# ESP32_Breakout.net
KiCad netlist of a schematic drawn in EAGLE
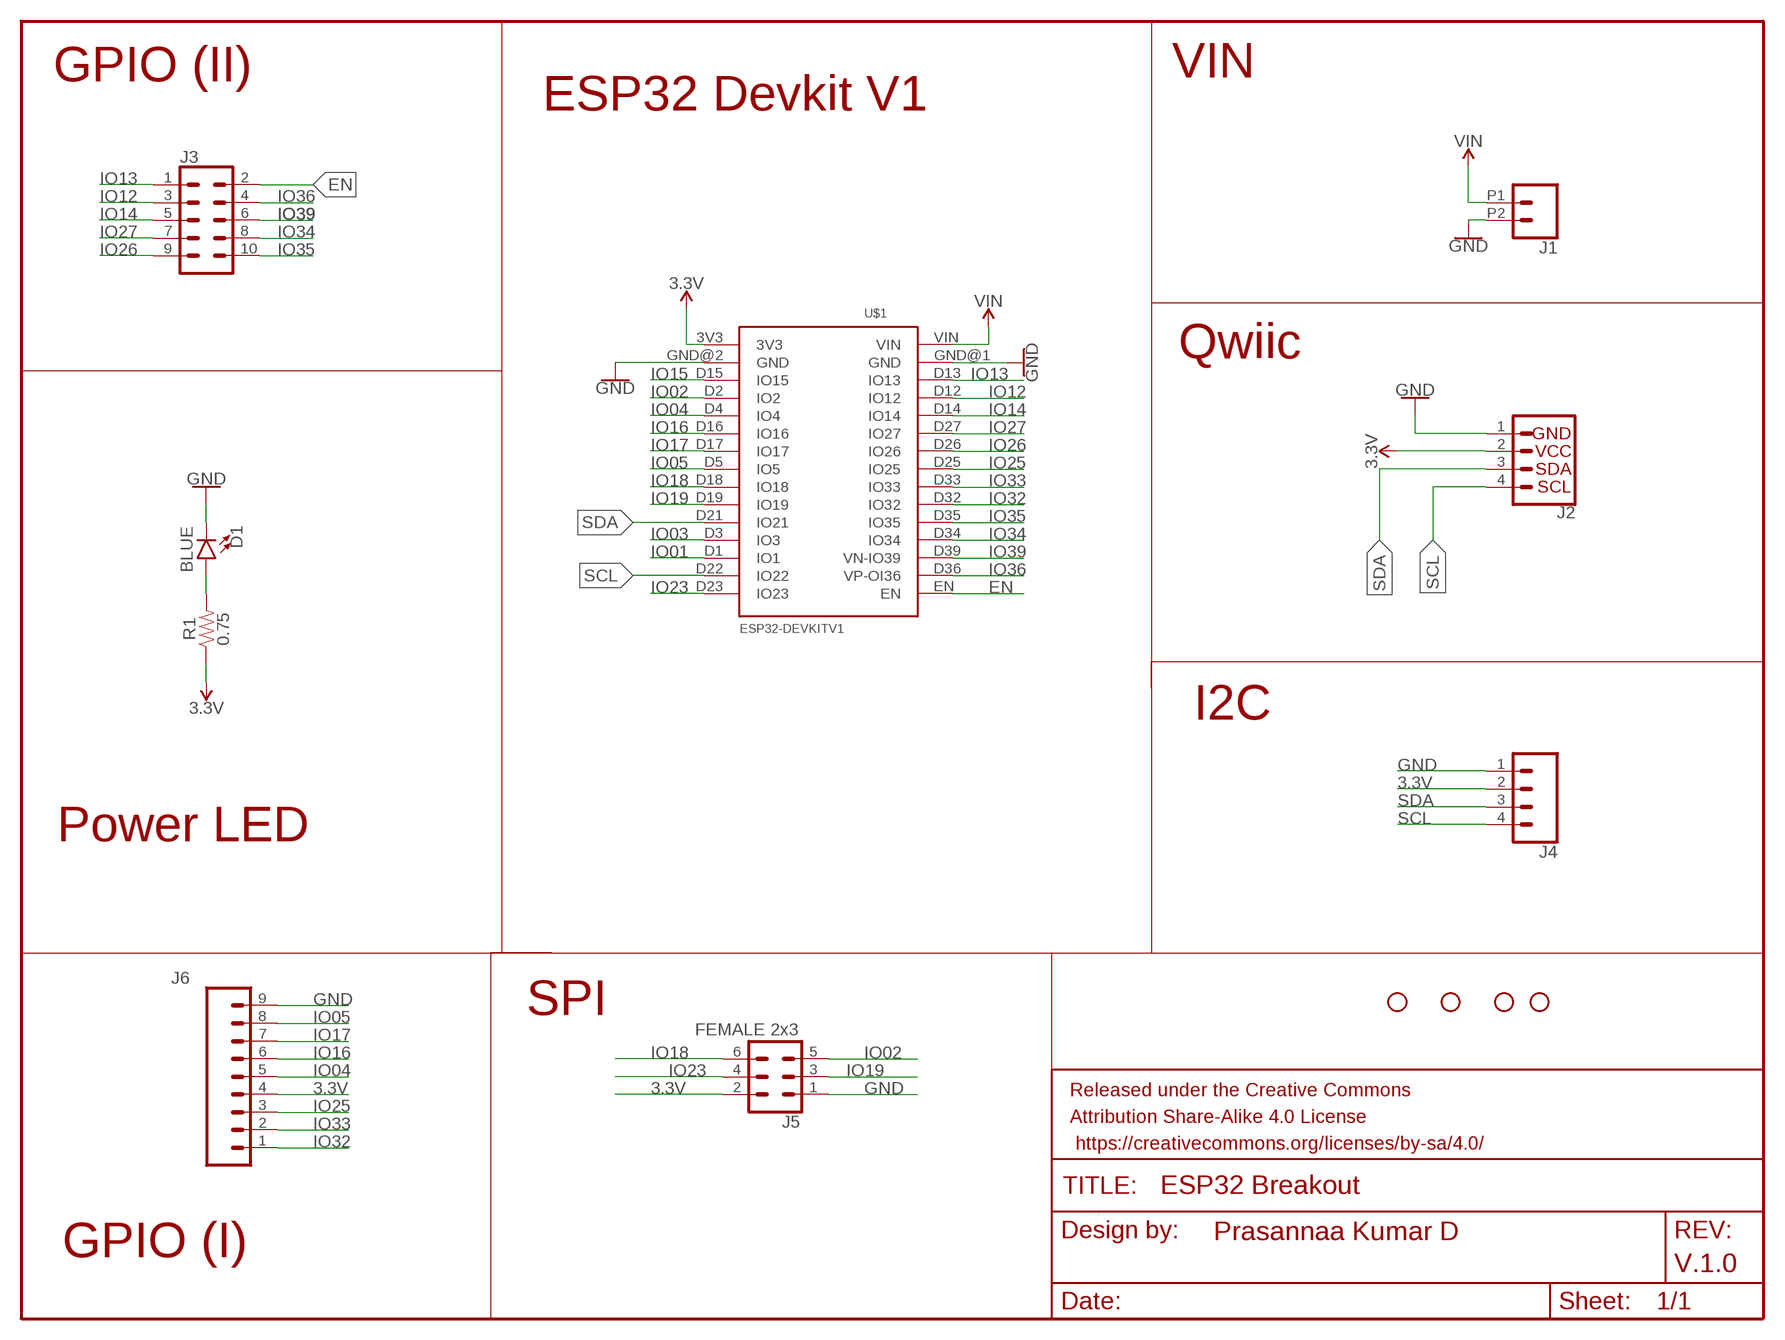
[diagram p0: schematic, sheet 1]

(export (version "E")
  (design (tool "Eeschema 10.0.6"))
  (components
    (comp (ref "D1")
      (value "BLUE")
      (footprint "eagle-import:LED-1206")
      (libsource (lib "eagle-import") (part "LED-BLUE1206"))
    )
    (comp (ref "FRAME1")
      (value "FRAME-LETTER")
      (footprint "eagle-import:CREATIVE_COMMONS")
      (fields (field (name "DESIGNER") "Prasannaa Kumar D") (field (name "REV") "V.1.0"))
      (libsource (lib "eagle-import") (part "FRAME-LETTER"))
    )
    (comp (ref "H1")
      (value "STAND-OFFTIGHT")
      (footprint "eagle-import:STAND-OFF-TIGHT")
      (libsource (lib "eagle-import") (part "STAND-OFFTIGHT"))
    )
    (comp (ref "H2")
      (value "STAND-OFFTIGHT")
      (footprint "eagle-import:STAND-OFF-TIGHT")
      (libsource (lib "eagle-import") (part "STAND-OFFTIGHT"))
    )
    (comp (ref "H3")
      (value "STAND-OFFTIGHT")
      (footprint "eagle-import:STAND-OFF-TIGHT")
      (libsource (lib "eagle-import") (part "STAND-OFFTIGHT"))
    )
    (comp (ref "H4")
      (value "STAND-OFFTIGHT")
      (footprint "eagle-import:STAND-OFF-TIGHT")
      (libsource (lib "eagle-import") (part "STAND-OFFTIGHT"))
    )
    (comp (ref "J1")
      (value "CONN_022.54MM_SCREWTERM")
      (footprint "eagle-import:1X02_2.54_SCREWTERM")
      (libsource (lib "eagle-import") (part "CONN_022.54MM_SCREWTERM"))
    )
    (comp (ref "J2")
      (value "QWIIC_CONNECTORJS-1MM")
      (footprint "eagle-import:1X04_1MM_RA")
      (libsource (lib "eagle-import") (part "QWIIC_CONNECTORJS-1MM"))
    )
    (comp (ref "J3")
      (value "CONN_05X2SHD")
      (footprint "eagle-import:2X5-SHROUDED")
      (libsource (lib "eagle-import") (part "CONN_05X2SHD"))
    )
    (comp (ref "J4")
      (value "CONN_041X04_NO_SILK")
      (footprint "eagle-import:1X04_NO_SILK")
      (libsource (lib "eagle-import") (part "CONN_041X04_NO_SILK"))
    )
    (comp (ref "J5")
      (value "FEMALE 2x3")
      (footprint "eagle-import:2X3")
      (libsource (lib "eagle-import") (part "CONN_03X2FEMALE"))
    )
    (comp (ref "J6")
      (value "CONN_09NO_SILK")
      (footprint "eagle-import:1X09_NO_SILK")
      (libsource (lib "eagle-import") (part "CONN_09NO_SILK"))
    )
    (comp (ref "R1")
      (value "0.75")
      (footprint "eagle-import:0805")
      (libsource (lib "eagle-import") (part "0.75OHM-0805-1/4W-1%"))
    )
    (comp (ref "U$1")
      (value "ESP32DEVKITV1")
      (footprint "eagle-import:ESP32-DEVKITV1")
      (libsource (lib "eagle-import") (part "ESP32DEVKITV1"))
    )
  )
  (nets
    (net (code "1") (name "/IO01") (class "Default")
      (node (ref "U$1") (pin "D1") (pinfunction "IO1_D1") (pintype "bidirectional"))
    )
    (net (code "2") (name "/IO02") (class "Default")
      (node (ref "J5") (pin "5") (pinfunction "5_5") (pintype "bidirectional"))
      (node (ref "U$1") (pin "D2") (pinfunction "IO2_D2") (pintype "bidirectional"))
    )
    (net (code "3") (name "/IO03") (class "Default")
      (node (ref "U$1") (pin "D3") (pinfunction "IO3_D3") (pintype "bidirectional"))
    )
    (net (code "4") (name "/IO04") (class "Default")
      (node (ref "J6") (pin "5") (pinfunction "5_5") (pintype "passive"))
      (node (ref "U$1") (pin "D4") (pinfunction "IO4_D4") (pintype "bidirectional"))
    )
    (net (code "5") (name "/IO05") (class "Default")
      (node (ref "J6") (pin "8") (pinfunction "8_8") (pintype "passive"))
      (node (ref "U$1") (pin "D5") (pinfunction "IO5_D5") (pintype "bidirectional"))
    )
    (net (code "6") (name "/IO12") (class "Default")
      (node (ref "J3") (pin "3") (pinfunction "3_3") (pintype "passive"))
      (node (ref "U$1") (pin "D12") (pinfunction "IO12_D12") (pintype "bidirectional"))
    )
    (net (code "7") (name "/IO13") (class "Default")
      (node (ref "J3") (pin "1") (pinfunction "1_1") (pintype "passive"))
      (node (ref "U$1") (pin "D13") (pinfunction "IO13_D13") (pintype "bidirectional"))
    )
    (net (code "8") (name "/IO14") (class "Default")
      (node (ref "J3") (pin "5") (pinfunction "5_5") (pintype "passive"))
      (node (ref "U$1") (pin "D14") (pinfunction "IO14_D14") (pintype "bidirectional"))
    )
    (net (code "9") (name "/IO15") (class "Default")
      (node (ref "U$1") (pin "D15") (pinfunction "IO15_D15") (pintype "bidirectional"))
    )
    (net (code "10") (name "/IO16") (class "Default")
      (node (ref "J6") (pin "6") (pinfunction "6_6") (pintype "passive"))
      (node (ref "U$1") (pin "D16") (pinfunction "IO16_D16") (pintype "bidirectional"))
    )
    (net (code "11") (name "/IO17") (class "Default")
      (node (ref "J6") (pin "7") (pinfunction "7_7") (pintype "passive"))
      (node (ref "U$1") (pin "D17") (pinfunction "IO17_D17") (pintype "bidirectional"))
    )
    (net (code "12") (name "/IO18") (class "Default")
      (node (ref "J5") (pin "6") (pinfunction "6_6") (pintype "bidirectional"))
      (node (ref "U$1") (pin "D18") (pinfunction "IO18_D18") (pintype "bidirectional"))
    )
    (net (code "13") (name "/IO19") (class "Default")
      (node (ref "J5") (pin "3") (pinfunction "3_3") (pintype "bidirectional"))
      (node (ref "U$1") (pin "D19") (pinfunction "IO19_D19") (pintype "bidirectional"))
    )
    (net (code "14") (name "/IO23") (class "Default")
      (node (ref "J5") (pin "4") (pinfunction "4_4") (pintype "bidirectional"))
      (node (ref "U$1") (pin "D23") (pinfunction "IO23_D23") (pintype "bidirectional"))
    )
    (net (code "15") (name "/IO25") (class "Default")
      (node (ref "J6") (pin "3") (pinfunction "3_3") (pintype "passive"))
      (node (ref "U$1") (pin "D25") (pinfunction "IO25_D25") (pintype "bidirectional"))
    )
    (net (code "16") (name "/IO26") (class "Default")
      (node (ref "J3") (pin "9") (pinfunction "9_9") (pintype "passive"))
      (node (ref "U$1") (pin "D26") (pinfunction "IO26_D26") (pintype "bidirectional"))
    )
    (net (code "17") (name "/IO27") (class "Default")
      (node (ref "J3") (pin "7") (pinfunction "7_7") (pintype "passive"))
      (node (ref "U$1") (pin "D27") (pinfunction "IO27_D27") (pintype "bidirectional"))
    )
    (net (code "18") (name "/IO32") (class "Default")
      (node (ref "J6") (pin "1") (pinfunction "1_1") (pintype "passive"))
      (node (ref "U$1") (pin "D32") (pinfunction "IO32_D32") (pintype "bidirectional"))
    )
    (net (code "19") (name "/IO33") (class "Default")
      (node (ref "J6") (pin "2") (pinfunction "2_2") (pintype "passive"))
      (node (ref "U$1") (pin "D33") (pinfunction "IO33_D33") (pintype "bidirectional"))
    )
    (net (code "20") (name "/IO34") (class "Default")
      (node (ref "J3") (pin "8") (pinfunction "8_8") (pintype "passive"))
      (node (ref "U$1") (pin "D34") (pinfunction "IO34_D34") (pintype "bidirectional"))
    )
    (net (code "21") (name "/IO35") (class "Default")
      (node (ref "J3") (pin "10") (pinfunction "10_10") (pintype "passive"))
      (node (ref "U$1") (pin "D35") (pinfunction "IO35_D35") (pintype "bidirectional"))
    )
    (net (code "22") (name "/IO36") (class "Default")
      (node (ref "J3") (pin "4") (pinfunction "4_4") (pintype "passive"))
      (node (ref "U$1") (pin "D36") (pinfunction "VP-OI36_D36") (pintype "bidirectional"))
    )
    (net (code "23") (name "/IO39") (class "Default")
      (node (ref "J3") (pin "6") (pinfunction "6_6") (pintype "passive"))
      (node (ref "U$1") (pin "D39") (pinfunction "VN-IO39_D39") (pintype "bidirectional"))
    )
    (net (code "24") (name "3.3V") (class "Default")
      (node (ref "J2") (pin "2") (pinfunction "VCC_2") (pintype "power_in"))
      (node (ref "J4") (pin "2") (pinfunction "2_2") (pintype "passive"))
      (node (ref "J5") (pin "2") (pinfunction "2_2") (pintype "bidirectional"))
      (node (ref "J6") (pin "4") (pinfunction "4_4") (pintype "passive"))
      (node (ref "R1") (pin "1") (pinfunction "1_1") (pintype "passive"))
      (node (ref "U$1") (pin "3V3") (pinfunction "3V3_3V3") (pintype "bidirectional"))
    )
    (net (code "25") (name "EN") (class "Default")
      (node (ref "J3") (pin "2") (pinfunction "2_2") (pintype "passive"))
      (node (ref "U$1") (pin "EN") (pinfunction "EN_EN") (pintype "bidirectional"))
    )
    (net (code "26") (name "GND") (class "Default")
      (node (ref "D1") (pin "C") (pinfunction "C_C") (pintype "passive"))
      (node (ref "J1") (pin "P2") (pinfunction "2_P2") (pintype "passive"))
      (node (ref "J2") (pin "1") (pinfunction "GND_1") (pintype "power_in"))
      (node (ref "J4") (pin "1") (pinfunction "1_1") (pintype "passive"))
      (node (ref "J5") (pin "1") (pinfunction "1_1") (pintype "bidirectional"))
      (node (ref "J6") (pin "9") (pinfunction "9_9") (pintype "passive"))
      (node (ref "U$1") (pin "GND@1") (pinfunction "GND_GND@1") (pintype "bidirectional"))
      (node (ref "U$1") (pin "GND@2") (pinfunction "GND_GND@2") (pintype "bidirectional"))
    )
    (net (code "27") (name "Net-(D1-PadA)") (class "Default")
      (node (ref "D1") (pin "A") (pinfunction "A_A") (pintype "passive"))
      (node (ref "R1") (pin "2") (pinfunction "2_2") (pintype "passive"))
    )
    (net (code "28") (name "SCL") (class "Default")
      (node (ref "J2") (pin "4") (pinfunction "SCL_4") (pintype "passive"))
      (node (ref "J4") (pin "4") (pinfunction "4_4") (pintype "passive"))
      (node (ref "U$1") (pin "D22") (pinfunction "IO22_D22") (pintype "bidirectional"))
    )
    (net (code "29") (name "SDA") (class "Default")
      (node (ref "J2") (pin "3") (pinfunction "SDA_3") (pintype "passive"))
      (node (ref "J4") (pin "3") (pinfunction "3_3") (pintype "passive"))
      (node (ref "U$1") (pin "D21") (pinfunction "IO21_D21") (pintype "bidirectional"))
    )
    (net (code "30") (name "VIN") (class "Default")
      (node (ref "J1") (pin "P1") (pinfunction "1_P1") (pintype "passive"))
      (node (ref "U$1") (pin "VIN") (pinfunction "VIN_VIN") (pintype "bidirectional"))
    )
  )
)
